# isoJTAG-FTDI.net
KiCad netlist of a schematic drawn in Altium Designer
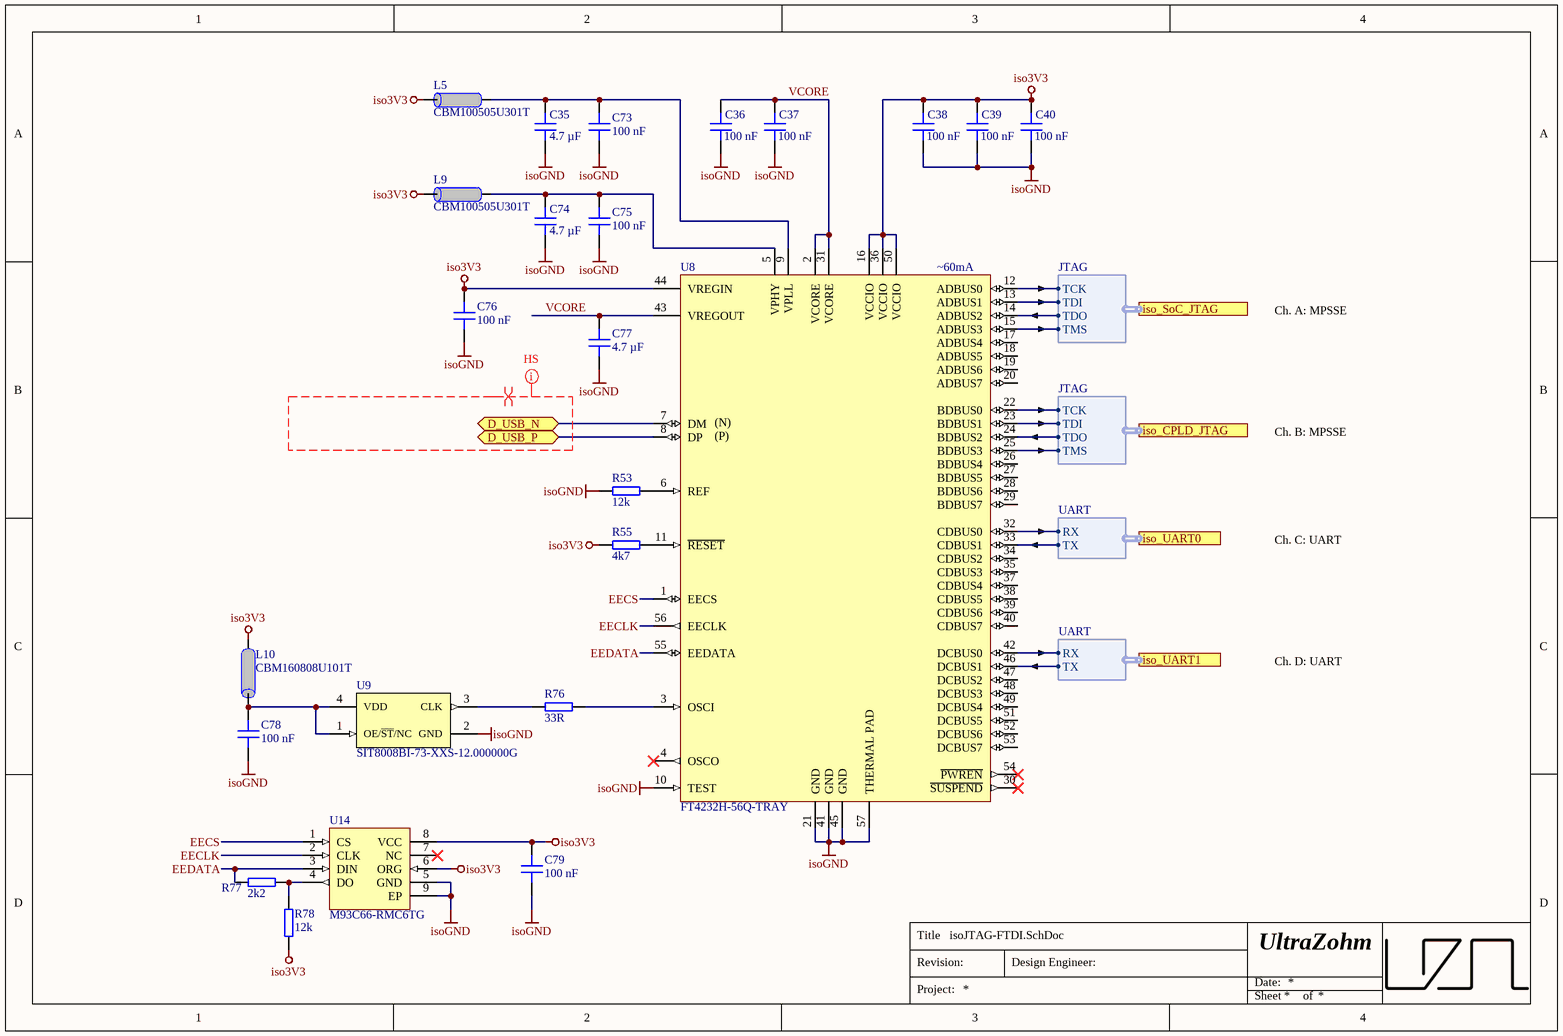
[diagram p0: isoJTAG-FTDI.SchDoc]

(export (version "E")
  (design (tool "Eeschema 10.0.6"))
  (components
    (comp (ref "C35")
      (value "4.7 µF")
      (footprint "C_0402_TE")
      (description "6.3V 4.7uF X5R ±20% 0402 Multilayer Ceramic Capacitors MLCC - SMD/SMT ROHS")
      (fields
        (field (name "MANUFACTURER PART NUMBER") "CL05A475MQ5NRNC")
        (field (name "MANUFACTURER") "Samsung Electro-Mechanics")
        (field (name "CREATED FROM") "AGeiger")
      )
      (libsource (lib "user") (part "Capacitor"))
    )
    (comp (ref "C36")
      (value "100 nF")
      (footprint "C_0402_TE")
      (description "50V 100nF X7R ±10% 0402 Multilayer Ceramic Capacitors MLCC - SMD/SMT ROHS")
      (fields
        (field (name "MANUFACTURER PART NUMBER") "GRM155R71H104KE14D")
        (field (name "MANUFACTURER") "Murata Electronics")
        (field (name "CREATED FROM") "AGeiger")
      )
      (libsource (lib "user") (part "Capacitor"))
    )
    (comp (ref "C37")
      (value "100 nF")
      (footprint "C_0402_TE")
      (description "50V 100nF X7R ±10% 0402 Multilayer Ceramic Capacitors MLCC - SMD/SMT ROHS")
      (fields
        (field (name "MANUFACTURER PART NUMBER") "GRM155R71H104KE14D")
        (field (name "MANUFACTURER") "Murata Electronics")
        (field (name "CREATED FROM") "AGeiger")
      )
      (libsource (lib "user") (part "Capacitor"))
    )
    (comp (ref "C38")
      (value "100 nF")
      (footprint "C_0402_TE")
      (description "50V 100nF X7R ±10% 0402 Multilayer Ceramic Capacitors MLCC - SMD/SMT ROHS")
      (fields
        (field (name "MANUFACTURER PART NUMBER") "GRM155R71H104KE14D")
        (field (name "MANUFACTURER") "Murata Electronics")
        (field (name "CREATED FROM") "AGeiger")
      )
      (libsource (lib "user") (part "Capacitor"))
    )
    (comp (ref "C39")
      (value "100 nF")
      (footprint "C_0402_TE")
      (description "50V 100nF X7R ±10% 0402 Multilayer Ceramic Capacitors MLCC - SMD/SMT ROHS")
      (fields
        (field (name "MANUFACTURER PART NUMBER") "GRM155R71H104KE14D")
        (field (name "MANUFACTURER") "Murata Electronics")
        (field (name "CREATED FROM") "AGeiger")
      )
      (libsource (lib "user") (part "Capacitor"))
    )
    (comp (ref "C40")
      (value "100 nF")
      (footprint "C_0402_TE")
      (description "50V 100nF X7R ±10% 0402 Multilayer Ceramic Capacitors MLCC - SMD/SMT ROHS")
      (fields
        (field (name "MANUFACTURER PART NUMBER") "GRM155R71H104KE14D")
        (field (name "MANUFACTURER") "Murata Electronics")
        (field (name "CREATED FROM") "AGeiger")
      )
      (libsource (lib "user") (part "Capacitor"))
    )
    (comp (ref "C73")
      (value "100 nF")
      (footprint "C_0402_TE")
      (description "50V 100nF X7R ±10% 0402 Multilayer Ceramic Capacitors MLCC - SMD/SMT ROHS")
      (fields
        (field (name "MANUFACTURER PART NUMBER") "GRM155R71H104KE14D")
        (field (name "MANUFACTURER") "Murata Electronics")
        (field (name "CREATED FROM") "AGeiger")
      )
      (libsource (lib "user") (part "Capacitor"))
    )
    (comp (ref "C74")
      (value "4.7 µF")
      (footprint "C_0402_TE")
      (description "6.3V 4.7uF X5R ±20% 0402 Multilayer Ceramic Capacitors MLCC - SMD/SMT ROHS")
      (fields
        (field (name "MANUFACTURER PART NUMBER") "CL05A475MQ5NRNC")
        (field (name "MANUFACTURER") "Samsung Electro-Mechanics")
        (field (name "CREATED FROM") "AGeiger")
      )
      (libsource (lib "user") (part "Capacitor"))
    )
    (comp (ref "C75")
      (value "100 nF")
      (footprint "C_0402_TE")
      (description "50V 100nF X7R ±10% 0402 Multilayer Ceramic Capacitors MLCC - SMD/SMT ROHS")
      (fields
        (field (name "MANUFACTURER PART NUMBER") "GRM155R71H104KE14D")
        (field (name "MANUFACTURER") "Murata Electronics")
        (field (name "CREATED FROM") "AGeiger")
      )
      (libsource (lib "user") (part "Capacitor"))
    )
    (comp (ref "C76")
      (value "100 nF")
      (footprint "C_0402_TE")
      (description "50V 100nF X7R ±10% 0402 Multilayer Ceramic Capacitors MLCC - SMD/SMT ROHS")
      (fields
        (field (name "MANUFACTURER PART NUMBER") "GRM155R71H104KE14D")
        (field (name "MANUFACTURER") "Murata Electronics")
        (field (name "CREATED FROM") "AGeiger")
      )
      (libsource (lib "user") (part "Capacitor"))
    )
    (comp (ref "C77")
      (value "4.7 µF")
      (footprint "C_0402_TE")
      (description "6.3V 4.7uF X5R ±20% 0402 Multilayer Ceramic Capacitors MLCC - SMD/SMT ROHS")
      (fields
        (field (name "MANUFACTURER PART NUMBER") "CL05A475MQ5NRNC")
        (field (name "MANUFACTURER") "Samsung Electro-Mechanics")
        (field (name "CREATED FROM") "AGeiger")
      )
      (libsource (lib "user") (part "Capacitor"))
    )
    (comp (ref "C78")
      (value "100 nF")
      (footprint "C_0402_TE")
      (description "50V 100nF X7R ±10% 0402 Multilayer Ceramic Capacitors MLCC - SMD/SMT ROHS")
      (fields
        (field (name "MANUFACTURER PART NUMBER") "GRM155R71H104KE14D")
        (field (name "MANUFACTURER") "Murata Electronics")
        (field (name "CREATED FROM") "AGeiger")
      )
      (libsource (lib "user") (part "Capacitor"))
    )
    (comp (ref "C79")
      (value "100 nF")
      (footprint "C_0402_TE")
      (description "50V 100nF X7R ±10% 0402 Multilayer Ceramic Capacitors MLCC - SMD/SMT ROHS")
      (fields
        (field (name "MANUFACTURER PART NUMBER") "GRM155R71H104KE14D")
        (field (name "MANUFACTURER") "Murata Electronics")
        (field (name "CREATED FROM") "AGeiger")
      )
      (libsource (lib "user") (part "Capacitor"))
    )
    (comp (ref "L5")
      (value "CBM100505U301T")
      (footprint "IND_0402_TE")
      (description "300mΩ ±25% 300Ω@100MHz 0402 Ferrite Beads ROHS")
      (fields
        (field (name "MANUFACTURER") "FH (Guangdong Fenghua Advanced Tech)")
        (field (name "LCSC PART NUMBER") "C394406")
        (field (name "CREATED FROM") "AGeiger")
      )
      (libsource (lib "user") (part "Ferrite_Bead"))
    )
    (comp (ref "L9")
      (value "CBM100505U301T")
      (footprint "IND_0402_TE")
      (description "300mΩ ±25% 300Ω@100MHz 0402 Ferrite Beads ROHS")
      (fields
        (field (name "MANUFACTURER") "FH (Guangdong Fenghua Advanced Tech)")
        (field (name "LCSC PART NUMBER") "C394406")
        (field (name "CREATED FROM") "AGeiger")
      )
      (libsource (lib "user") (part "Ferrite_Bead"))
    )
    (comp (ref "L10")
      (value "CBM160808U101T")
      (footprint "IND_0603_TE")
      (description "60mΩ ±25% 100Ω@100MHz 0603 Ferrite Beads ROHS")
      (fields
        (field (name "MANUFACTURER") "FH (Guangdong Fenghua Advanced Tech)")
        (field (name "LCSC PART NUMBER") "C361675")
        (field (name "CREATED FROM") "AGeiger")
      )
      (libsource (lib "") (part "Ferrite_Bead_1"))
    )
    (comp (ref "R53")
      (value "12k")
      (footprint "R_0402_TE")
      (description "62.5mW Thick Film Resistors ±100ppm/℃ ±1% 12kΩ 0402 Chip Resistor - Surface Mount ROHS")
      (fields
        (field (name "MANUFACTURER PART NUMBER") "RC0402FR-0712KL")
        (field (name "MANUFACTURER") "YAGEO")
        (field (name "CREATED FROM") "AGeiger")
      )
      (libsource (lib "user") (part "Resistor"))
    )
    (comp (ref "R55")
      (value "4k7")
      (footprint "R_0402_TE")
      (description "62.5mW Thick Film Resistors ±100ppm/℃ ±1% 4.7kΩ 0402 Chip Resistor - Surface Mount ROHS")
      (fields
        (field (name "MANUFACTURER PART NUMBER") "RC0402FR-074K7L")
        (field (name "MANUFACTURER") "YAGEO")
        (field (name "CREATED FROM") "AGeiger")
      )
      (libsource (lib "user") (part "Resistor"))
    )
    (comp (ref "R76")
      (value "33R")
      (footprint "R_0402_TE")
      (description "62.5mW Thick Film Resistors ±100ppm/℃ ±1% 33Ω 0402 Chip Resistor - Surface Mount ROHS")
      (fields
        (field (name "MANUFACTURER PART NUMBER") "RC0402FR-0733RL")
        (field (name "MANUFACTURER") "YAGEO")
        (field (name "CREATED FROM") "AGeiger")
      )
      (libsource (lib "user") (part "Resistor"))
    )
    (comp (ref "R77")
      (value "2k2")
      (footprint "R_0402_TE")
      (description "62.5mW Thick Film Resistors ±100ppm/℃ ±1% 2.2kΩ 0402 Chip Resistor - Surface Mount ROHS")
      (fields
        (field (name "MANUFACTURER PART NUMBER") "RC0402FR-072K2L")
        (field (name "MANUFACTURER") "YAGEO")
        (field (name "CREATED FROM") "AGeiger")
      )
      (libsource (lib "user") (part "Resistor"))
    )
    (comp (ref "R78")
      (value "12k")
      (footprint "R_0402_TE")
      (description "62.5mW Thick Film Resistors ±100ppm/℃ ±1% 12kΩ 0402 Chip Resistor - Surface Mount ROHS")
      (fields
        (field (name "MANUFACTURER PART NUMBER") "RC0402FR-0712KL")
        (field (name "MANUFACTURER") "YAGEO")
        (field (name "CREATED FROM") "AGeiger")
      )
      (libsource (lib "user") (part "Resistor"))
    )
    (comp (ref "U8")
      (value "FT4232H-56Q-TRAY")
      (footprint "QFN50P800X800-57T610X610N")
      (description "USB Interface IC Quad 480Mbs 4 UART USB 2.0 12Mbit")
      (fields
        (field (name "MANUFACTURER") "FTDI")
        (field (name "LCSC PART NUMBER") "C1521561")
        (field (name "CREATED FROM") "AGeiger")
      )
      (libsource (lib "user") (part "FT4232H-56Q"))
    )
    (comp (ref "U9")
      (value "SIT8008BI-73-XXS-12.000000G")
      (footprint "2016")
      (description "Clock-Standardoszillatoren -40 to 85C, 2016, 50ppm, 2.25V-3.63V, 12MHz, ST, 250 pcs T&R 8 mm")
      (fields
        (field (name "MANUFACTURER") "SiTime")
        (field (name "LCSC PART NUMBER") "C1508636")
        (field (name "CREATED FROM") "AGeiger")
      )
      (libsource (lib "user") (part "SiT8103"))
    )
    (comp (ref "U14")
      (value "M93C66-RMC6TG")
      (footprint "UFDFPN8")
      (description "4Kbit MICROWIRE EE 1.8 V to 5.5 V")
      (fields
        (field (name "MANUFACTURER") "STMicroelectronics")
        (field (name "LCSC PART NUMBER") "C2061956")
        (field (name "CREATED FROM") "AGeiger")
      )
      (libsource (lib "user") (part "M93C46-MN6P"))
    )
  )
  (nets
    (net (code "3") (name "/D_USB_N") (class "Default")
      (node (ref "U8") (pin "7") (pinfunction "DM_7") (pintype "bidirectional"))
    )
    (net (code "4") (name "/D_USB_P") (class "Default")
      (node (ref "U8") (pin "8") (pinfunction "DP_8") (pintype "bidirectional"))
    )
    (net (code "5") (name "/EECLK") (class "Default")
      (node (ref "U14") (pin "2") (pinfunction "CLK_2") (pintype "input"))
      (node (ref "U8") (pin "56") (pinfunction "EECLK_56") (pintype "output"))
    )
    (net (code "6") (name "/EECS") (class "Default")
      (node (ref "U14") (pin "1") (pinfunction "CS_1") (pintype "input"))
      (node (ref "U8") (pin "1") (pinfunction "EECS_1") (pintype "bidirectional"))
    )
    (net (code "7") (name "/EEDATA") (class "Default")
      (node (ref "R77") (pin "1") (pinfunction "1_1") (pintype "passive"))
      (node (ref "U14") (pin "3") (pinfunction "DIN_3") (pintype "input"))
      (node (ref "U8") (pin "55") (pinfunction "EEDATA_55") (pintype "bidirectional"))
    )
    (net (code "8") (name "/VCORE") (class "Default")
      (node (ref "C36") (pin "2") (pinfunction "2_2") (pintype "passive"))
      (node (ref "C37") (pin "2") (pinfunction "2_2") (pintype "passive"))
      (node (ref "C77") (pin "2") (pinfunction "2_2") (pintype "passive"))
      (node (ref "U8") (pin "2") (pinfunction "VCORE_2") (pintype "power_in"))
      (node (ref "U8") (pin "31") (pinfunction "VCORE_31") (pintype "power_in"))
      (node (ref "U8") (pin "43") (pinfunction "VREGOUT_43") (pintype "power_in"))
    )
    (net (code "11") (name "Net-(U8-OSCI)") (class "Default")
      (node (ref "R76") (pin "2") (pinfunction "2_2") (pintype "passive"))
      (node (ref "U8") (pin "3") (pinfunction "OSCI_3") (pintype "input"))
    )
    (net (code "12") (name "Net-(U8-REF)") (class "Default")
      (node (ref "R53") (pin "2") (pinfunction "2_2") (pintype "passive"))
      (node (ref "U8") (pin "6") (pinfunction "REF_6") (pintype "input"))
    )
    (net (code "13") (name "Net-(U8-VPHY)") (class "Default")
      (node (ref "C74") (pin "2") (pinfunction "2_2") (pintype "passive"))
      (node (ref "C75") (pin "2") (pinfunction "2_2") (pintype "passive"))
      (node (ref "L9") (pin "1") (pinfunction "1_1") (pintype "passive"))
      (node (ref "U8") (pin "5") (pinfunction "VPHY_5") (pintype "power_in"))
    )
    (net (code "14") (name "Net-(U8-VPLL)") (class "Default")
      (node (ref "C35") (pin "2") (pinfunction "2_2") (pintype "passive"))
      (node (ref "C73") (pin "2") (pinfunction "2_2") (pintype "passive"))
      (node (ref "L5") (pin "1") (pinfunction "1_1") (pintype "passive"))
      (node (ref "U8") (pin "9") (pinfunction "VPLL_9") (pintype "power_in"))
    )
    (net (code "15") (name "Net-(U8-~{RESET})") (class "Default")
      (node (ref "R55") (pin "2") (pinfunction "2_2") (pintype "passive"))
      (node (ref "U8") (pin "11") (pinfunction "~{RESET}_11") (pintype "input"))
    )
    (net (code "16") (name "Net-(U9-CLK)") (class "Default")
      (node (ref "R76") (pin "1") (pinfunction "1_1") (pintype "passive"))
      (node (ref "U9") (pin "3") (pinfunction "CLK_3") (pintype "output"))
    )
    (net (code "17") (name "Net-(U9-OE{slash}~{ST}{slash}NC)") (class "Default")
      (node (ref "C78") (pin "2") (pinfunction "2_2") (pintype "passive"))
      (node (ref "L10") (pin "2") (pinfunction "2_2") (pintype "passive"))
      (node (ref "U9") (pin "1") (pinfunction "OE/~{ST}/NC_1") (pintype "input"))
      (node (ref "U9") (pin "4") (pinfunction "VDD_4") (pintype "power_in"))
    )
    (net (code "18") (name "Net-(U14-DO)") (class "Default")
      (node (ref "R77") (pin "2") (pinfunction "2_2") (pintype "passive"))
      (node (ref "R78") (pin "2") (pinfunction "2_2") (pintype "passive"))
      (node (ref "U14") (pin "4") (pinfunction "DO_4") (pintype "output"))
    )
    (net (code "19") (name "iso3V3") (class "Default")
      (node (ref "C38") (pin "2") (pinfunction "2_2") (pintype "passive"))
      (node (ref "C39") (pin "2") (pinfunction "2_2") (pintype "passive"))
      (node (ref "C40") (pin "2") (pinfunction "2_2") (pintype "passive"))
      (node (ref "C76") (pin "2") (pinfunction "2_2") (pintype "passive"))
      (node (ref "C79") (pin "2") (pinfunction "2_2") (pintype "passive"))
      (node (ref "L10") (pin "1") (pinfunction "1_1") (pintype "passive"))
      (node (ref "L5") (pin "2") (pinfunction "2_2") (pintype "passive"))
      (node (ref "L9") (pin "2") (pinfunction "2_2") (pintype "passive"))
      (node (ref "R55") (pin "1") (pinfunction "1_1") (pintype "passive"))
      (node (ref "R78") (pin "1") (pinfunction "1_1") (pintype "passive"))
      (node (ref "U14") (pin "6") (pinfunction "ORG_6") (pintype "input"))
      (node (ref "U14") (pin "8") (pinfunction "VCC_8") (pintype "power_in"))
      (node (ref "U8") (pin "16") (pinfunction "VCCIO_16") (pintype "power_in"))
      (node (ref "U8") (pin "36") (pinfunction "VCCIO_36") (pintype "power_in"))
      (node (ref "U8") (pin "44") (pinfunction "VREGIN_44") (pintype "power_in"))
      (node (ref "U8") (pin "50") (pinfunction "VCCIO_50") (pintype "power_in"))
    )
    (net (code "20") (name "isoGND") (class "Default")
      (node (ref "C35") (pin "1") (pinfunction "1_1") (pintype "passive"))
      (node (ref "C36") (pin "1") (pinfunction "1_1") (pintype "passive"))
      (node (ref "C37") (pin "1") (pinfunction "1_1") (pintype "passive"))
      (node (ref "C38") (pin "1") (pinfunction "1_1") (pintype "passive"))
      (node (ref "C39") (pin "1") (pinfunction "1_1") (pintype "passive"))
      (node (ref "C40") (pin "1") (pinfunction "1_1") (pintype "passive"))
      (node (ref "C73") (pin "1") (pinfunction "1_1") (pintype "passive"))
      (node (ref "C74") (pin "1") (pinfunction "1_1") (pintype "passive"))
      (node (ref "C75") (pin "1") (pinfunction "1_1") (pintype "passive"))
      (node (ref "C76") (pin "1") (pinfunction "1_1") (pintype "passive"))
      (node (ref "C77") (pin "1") (pinfunction "1_1") (pintype "passive"))
      (node (ref "C78") (pin "1") (pinfunction "1_1") (pintype "passive"))
      (node (ref "C79") (pin "1") (pinfunction "1_1") (pintype "passive"))
      (node (ref "R53") (pin "1") (pinfunction "1_1") (pintype "passive"))
      (node (ref "U14") (pin "5") (pinfunction "GND_5") (pintype "power_in"))
      (node (ref "U14") (pin "9") (pinfunction "EP_9") (pintype "power_in"))
      (node (ref "U8") (pin "10") (pinfunction "TEST_10") (pintype "input"))
      (node (ref "U8") (pin "21") (pinfunction "GND_21") (pintype "power_in"))
      (node (ref "U8") (pin "41") (pinfunction "GND_41") (pintype "power_in"))
      (node (ref "U8") (pin "45") (pinfunction "GND_45") (pintype "power_in"))
      (node (ref "U8") (pin "57") (pinfunction "THERMAL_PAD_57") (pintype "power_in"))
      (node (ref "U9") (pin "2") (pinfunction "GND_2") (pintype "power_in"))
    )
    (net (code "21") (name "unconnected-(U8-ADBUS0-Pad12)") (class "Default")
      (node (ref "U8") (pin "12") (pinfunction "ADBUS0_12") (pintype "bidirectional"))
    )
    (net (code "22") (name "unconnected-(U8-ADBUS1-Pad13)") (class "Default")
      (node (ref "U8") (pin "13") (pinfunction "ADBUS1_13") (pintype "bidirectional"))
    )
    (net (code "23") (name "unconnected-(U8-ADBUS2-Pad14)") (class "Default")
      (node (ref "U8") (pin "14") (pinfunction "ADBUS2_14") (pintype "bidirectional"))
    )
    (net (code "24") (name "unconnected-(U8-ADBUS3-Pad15)") (class "Default")
      (node (ref "U8") (pin "15") (pinfunction "ADBUS3_15") (pintype "bidirectional"))
    )
    (net (code "25") (name "unconnected-(U8-ADBUS4-Pad17)") (class "Default")
      (node (ref "U8") (pin "17") (pinfunction "ADBUS4_17") (pintype "bidirectional"))
    )
    (net (code "26") (name "unconnected-(U8-ADBUS5-Pad18)") (class "Default")
      (node (ref "U8") (pin "18") (pinfunction "ADBUS5_18") (pintype "bidirectional"))
    )
    (net (code "27") (name "unconnected-(U8-ADBUS6-Pad19)") (class "Default")
      (node (ref "U8") (pin "19") (pinfunction "ADBUS6_19") (pintype "bidirectional"))
    )
    (net (code "28") (name "unconnected-(U8-ADBUS7-Pad20)") (class "Default")
      (node (ref "U8") (pin "20") (pinfunction "ADBUS7_20") (pintype "bidirectional"))
    )
    (net (code "29") (name "unconnected-(U8-BDBUS0-Pad22)") (class "Default")
      (node (ref "U8") (pin "22") (pinfunction "BDBUS0_22") (pintype "bidirectional"))
    )
    (net (code "30") (name "unconnected-(U8-BDBUS1-Pad23)") (class "Default")
      (node (ref "U8") (pin "23") (pinfunction "BDBUS1_23") (pintype "bidirectional"))
    )
    (net (code "31") (name "unconnected-(U8-BDBUS2-Pad24)") (class "Default")
      (node (ref "U8") (pin "24") (pinfunction "BDBUS2_24") (pintype "bidirectional"))
    )
    (net (code "32") (name "unconnected-(U8-BDBUS3-Pad25)") (class "Default")
      (node (ref "U8") (pin "25") (pinfunction "BDBUS3_25") (pintype "bidirectional"))
    )
    (net (code "33") (name "unconnected-(U8-BDBUS4-Pad26)") (class "Default")
      (node (ref "U8") (pin "26") (pinfunction "BDBUS4_26") (pintype "bidirectional"))
    )
    (net (code "34") (name "unconnected-(U8-BDBUS5-Pad27)") (class "Default")
      (node (ref "U8") (pin "27") (pinfunction "BDBUS5_27") (pintype "bidirectional"))
    )
    (net (code "35") (name "unconnected-(U8-BDBUS6-Pad28)") (class "Default")
      (node (ref "U8") (pin "28") (pinfunction "BDBUS6_28") (pintype "bidirectional"))
    )
    (net (code "36") (name "unconnected-(U8-BDBUS7-Pad29)") (class "Default")
      (node (ref "U8") (pin "29") (pinfunction "BDBUS7_29") (pintype "bidirectional"))
    )
    (net (code "37") (name "unconnected-(U8-CDBUS0-Pad32)") (class "Default")
      (node (ref "U8") (pin "32") (pinfunction "CDBUS0_32") (pintype "bidirectional"))
    )
    (net (code "38") (name "unconnected-(U8-CDBUS1-Pad33)") (class "Default")
      (node (ref "U8") (pin "33") (pinfunction "CDBUS1_33") (pintype "bidirectional"))
    )
    (net (code "39") (name "unconnected-(U8-CDBUS2-Pad34)") (class "Default")
      (node (ref "U8") (pin "34") (pinfunction "CDBUS2_34") (pintype "bidirectional"))
    )
    (net (code "40") (name "unconnected-(U8-CDBUS3-Pad35)") (class "Default")
      (node (ref "U8") (pin "35") (pinfunction "CDBUS3_35") (pintype "bidirectional"))
    )
    (net (code "41") (name "unconnected-(U8-CDBUS4-Pad37)") (class "Default")
      (node (ref "U8") (pin "37") (pinfunction "CDBUS4_37") (pintype "bidirectional"))
    )
    (net (code "42") (name "unconnected-(U8-CDBUS5-Pad38)") (class "Default")
      (node (ref "U8") (pin "38") (pinfunction "CDBUS5_38") (pintype "bidirectional"))
    )
    (net (code "43") (name "unconnected-(U8-CDBUS6-Pad39)") (class "Default")
      (node (ref "U8") (pin "39") (pinfunction "CDBUS6_39") (pintype "bidirectional"))
    )
    (net (code "44") (name "unconnected-(U8-CDBUS7-Pad40)") (class "Default")
      (node (ref "U8") (pin "40") (pinfunction "CDBUS7_40") (pintype "bidirectional"))
    )
    (net (code "45") (name "unconnected-(U8-DCBUS0-Pad42)") (class "Default")
      (node (ref "U8") (pin "42") (pinfunction "DCBUS0_42") (pintype "bidirectional"))
    )
    (net (code "46") (name "unconnected-(U8-DCBUS1-Pad46)") (class "Default")
      (node (ref "U8") (pin "46") (pinfunction "DCBUS1_46") (pintype "bidirectional"))
    )
    (net (code "47") (name "unconnected-(U8-DCBUS2-Pad47)") (class "Default")
      (node (ref "U8") (pin "47") (pinfunction "DCBUS2_47") (pintype "bidirectional"))
    )
    (net (code "48") (name "unconnected-(U8-DCBUS3-Pad48)") (class "Default")
      (node (ref "U8") (pin "48") (pinfunction "DCBUS3_48") (pintype "bidirectional"))
    )
    (net (code "49") (name "unconnected-(U8-DCBUS4-Pad49)") (class "Default")
      (node (ref "U8") (pin "49") (pinfunction "DCBUS4_49") (pintype "bidirectional"))
    )
    (net (code "50") (name "unconnected-(U8-DCBUS5-Pad51)") (class "Default")
      (node (ref "U8") (pin "51") (pinfunction "DCBUS5_51") (pintype "bidirectional"))
    )
    (net (code "51") (name "unconnected-(U8-DCBUS6-Pad52)") (class "Default")
      (node (ref "U8") (pin "52") (pinfunction "DCBUS6_52") (pintype "bidirectional"))
    )
    (net (code "52") (name "unconnected-(U8-DCBUS7-Pad53)") (class "Default")
      (node (ref "U8") (pin "53") (pinfunction "DCBUS7_53") (pintype "bidirectional"))
    )
    (net (code "53") (name "unconnected-(U8-OSCO-Pad4)") (class "Default")
      (node (ref "U8") (pin "4") (pinfunction "OSCO_4") (pintype "output+no_connect"))
    )
    (net (code "54") (name "unconnected-(U8-~{PWREN}-Pad54)") (class "Default")
      (node (ref "U8") (pin "54") (pinfunction "~{PWREN}_54") (pintype "output+no_connect"))
    )
    (net (code "55") (name "unconnected-(U8-~{SUSPEND}-Pad30)") (class "Default")
      (node (ref "U8") (pin "30") (pinfunction "~{SUSPEND}_30") (pintype "output+no_connect"))
    )
    (net (code "56") (name "unconnected-(U14-NC-Pad7)") (class "Default")
      (node (ref "U14") (pin "7") (pinfunction "NC_7") (pintype "passive+no_connect"))
    )
  )
)
